# Fermento_1side.net
KiCad netlist of a schematic drawn in EAGLE
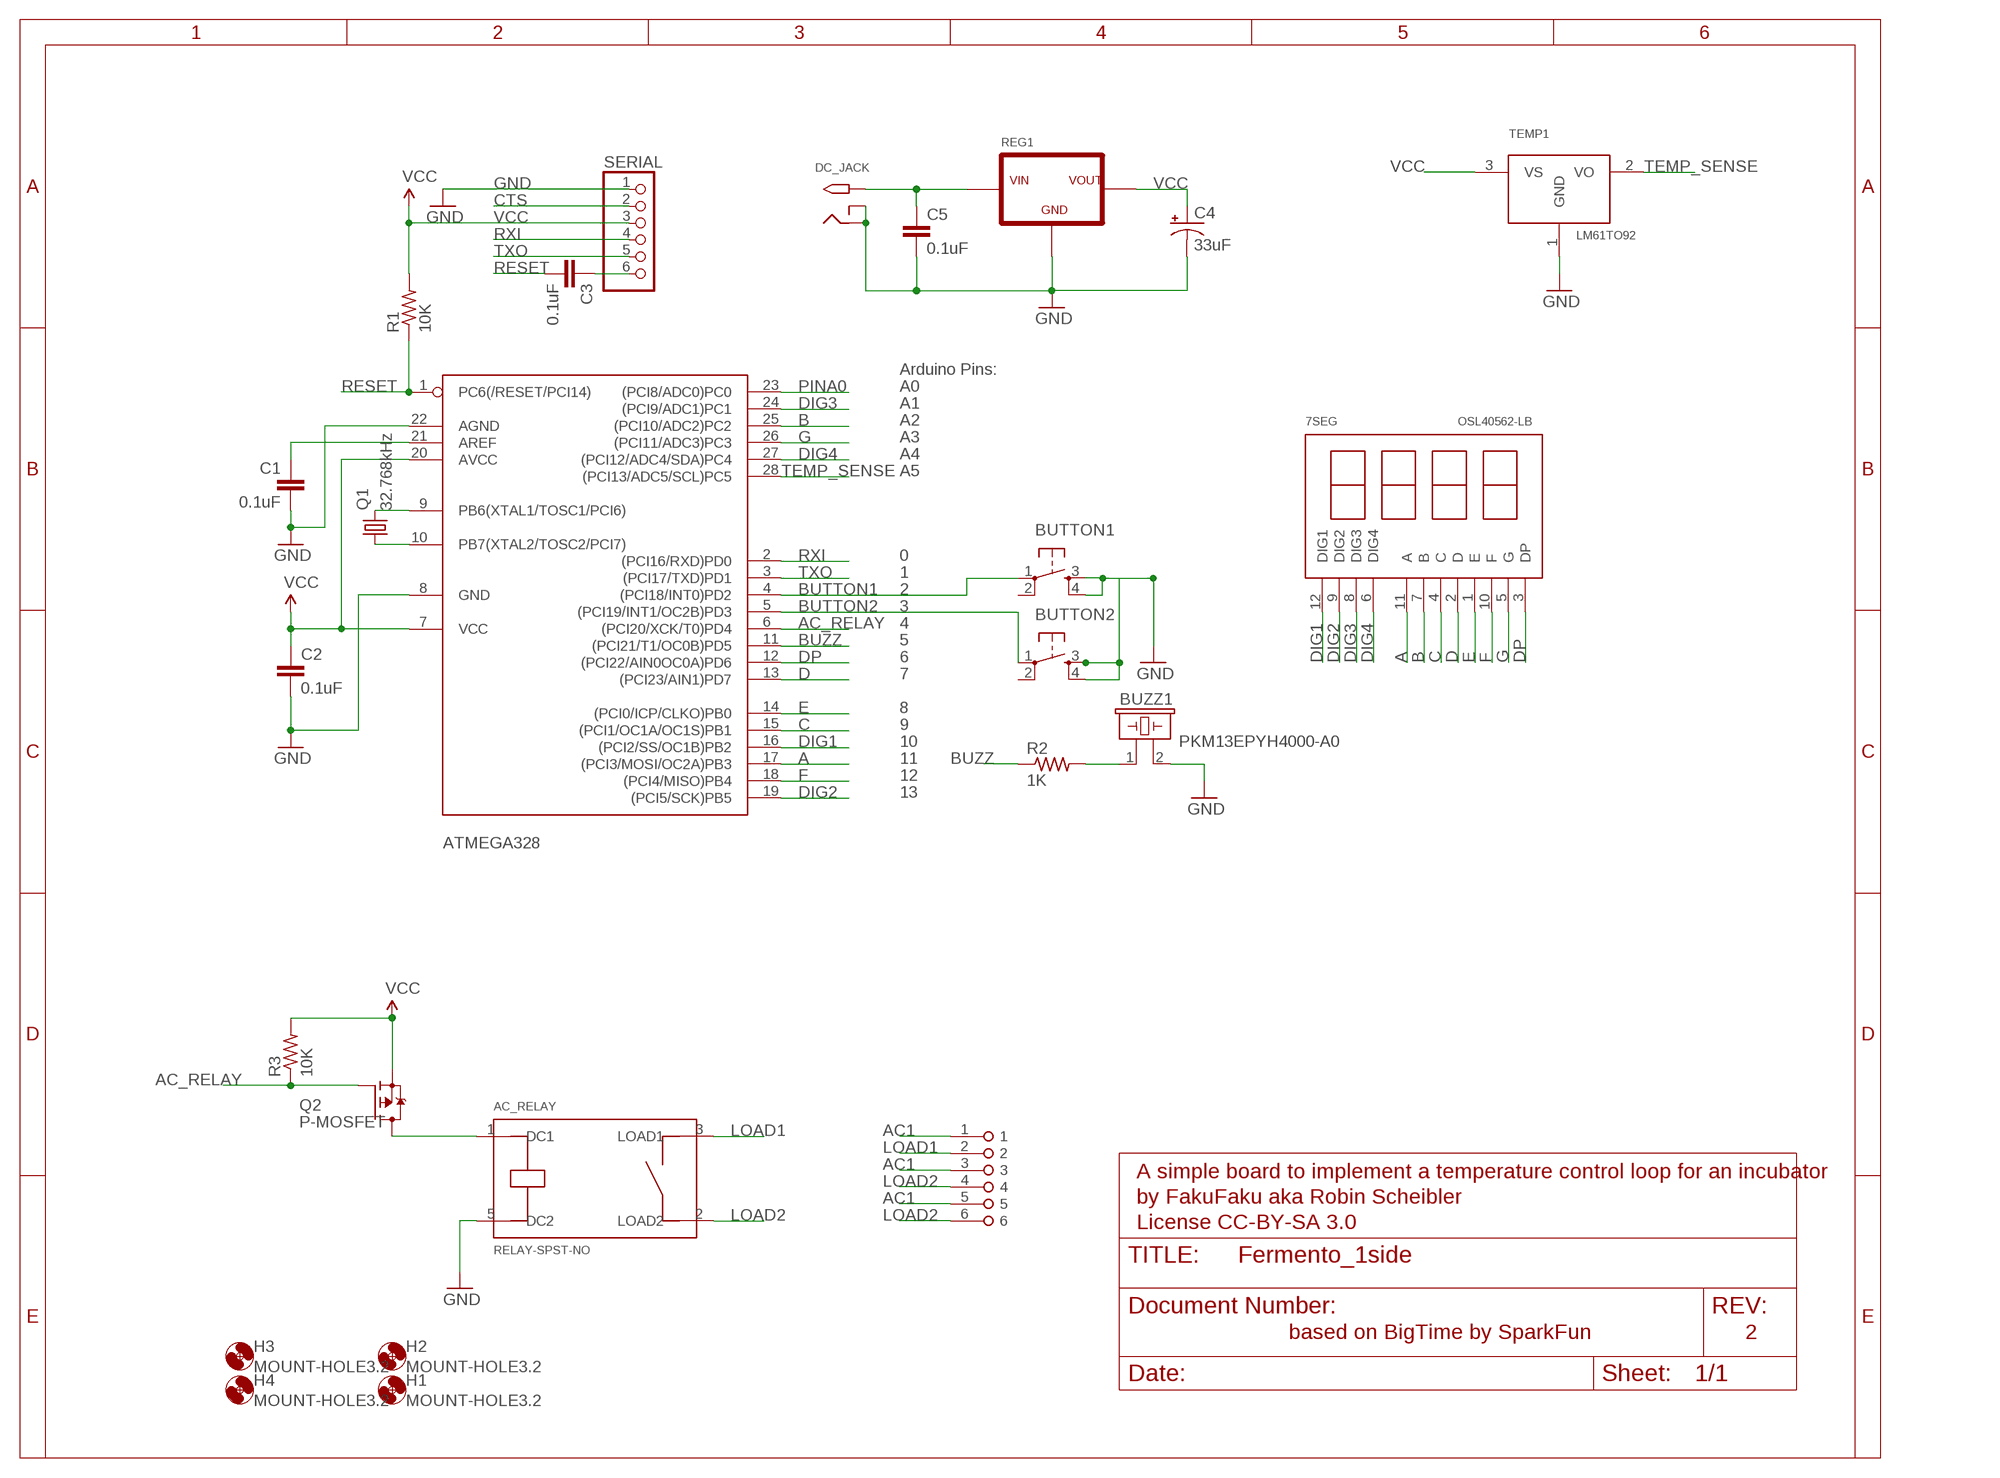
[diagram p0: schematic, sheet 1]

(export (version "E")
  (design (tool "Eeschema 10.0.6"))
  (components
    (comp (ref "7SEG")
      (value "OSL40562-LB")
      (footprint "eagle-import:OSL40562")
      (libsource (lib "eagle-import") (part "7SEG"))
    )
    (comp (ref "AC_RELAY")
      (value "RELAY-SPST-NO")
      (footprint "eagle-import:G6RL-1A-DC3")
      (libsource (lib "eagle-import") (part "RELAY-SPST-NO"))
    )
    (comp (ref "ATMEGA328")
      (value "ATMEGA168-20P")
      (footprint "eagle-import:DIL28-3")
      (libsource (lib "eagle-import") (part "ATMEGA168P-20"))
    )
    (comp (ref "BUTTON1")
      (value "TAC_SWITCHPTH")
      (footprint "eagle-import:TACTILE-PTH")
      (libsource (lib "eagle-import") (part "TAC_SWITCHPTH"))
    )
    (comp (ref "BUTTON2")
      (value "TAC_SWITCHPTH")
      (footprint "eagle-import:TACTILE-PTH")
      (libsource (lib "eagle-import") (part "TAC_SWITCHPTH"))
    )
    (comp (ref "BUZZ1")
      (value "PKM13EPYH4000-A0")
      (footprint "eagle-import:PIEZO-MURATA-13MM")
      (libsource (lib "eagle-import") (part "BUZZER13MM"))
    )
    (comp (ref "C1")
      (value "0.1uF")
      (footprint "eagle-import:CAP-PTH-SMALL")
      (libsource (lib "eagle-import") (part "CAPPTH"))
    )
    (comp (ref "C2")
      (value "0.1uF")
      (footprint "eagle-import:CAP-PTH-SMALL")
      (libsource (lib "eagle-import") (part "CAPPTH"))
    )
    (comp (ref "C3")
      (value "0.1uF")
      (footprint "eagle-import:CAP-PTH-SMALL")
      (libsource (lib "eagle-import") (part "CAPPTH"))
    )
    (comp (ref "C4")
      (value "33uF")
      (footprint "eagle-import:CPOL-RADIAL-10UF-25V")
      (libsource (lib "eagle-import") (part "CAP_POLPTH2"))
    )
    (comp (ref "C5")
      (value "0.1uF")
      (footprint "eagle-import:CAP-PTH-SMALL")
      (libsource (lib "eagle-import") (part "CAPPTH"))
    )
    (comp (ref "DC_JACK")
      (value "2.1MMJACKTHM")
      (footprint "eagle-import:PJ-102A")
      (libsource (lib "eagle-import") (part "2.1MMJACKTHM"))
    )
    (comp (ref "H1")
      (value "MOUNT-HOLE3.2")
      (footprint "eagle-import:3,2")
      (libsource (lib "eagle-import") (part "MOUNT-HOLE3.2"))
    )
    (comp (ref "H2")
      (value "MOUNT-HOLE3.2")
      (footprint "eagle-import:3,2")
      (libsource (lib "eagle-import") (part "MOUNT-HOLE3.2"))
    )
    (comp (ref "H3")
      (value "MOUNT-HOLE3.2")
      (footprint "eagle-import:3,2")
      (libsource (lib "eagle-import") (part "MOUNT-HOLE3.2"))
    )
    (comp (ref "H4")
      (value "MOUNT-HOLE3.2")
      (footprint "eagle-import:3,2")
      (libsource (lib "eagle-import") (part "MOUNT-HOLE3.2"))
    )
    (comp (ref "Q1")
      (value "32.768kHz")
      (footprint "eagle-import:CRYSTAL-8X3-TH")
      (libsource (lib "eagle-import") (part "CRYSTAL8X3"))
    )
    (comp (ref "Q2")
      (value "P-MOSFET")
      (footprint "eagle-import:TO92-")
      (libsource (lib "eagle-import") (part "P-MOSFET"))
    )
    (comp (ref "R1")
      (value "10K")
      (footprint "eagle-import:0207_10")
      (libsource (lib "eagle-import") (part "R-US_0207/10"))
    )
    (comp (ref "R2")
      (value "1K")
      (footprint "eagle-import:0207_10")
      (libsource (lib "eagle-import") (part "R-US_0207/10"))
    )
    (comp (ref "R3")
      (value "10K")
      (footprint "eagle-import:0207_10")
      (libsource (lib "eagle-import") (part "R-US_0207/10"))
    )
    (comp (ref "REG1")
      (value "REGULATOR-NOTHERMAL-TO220-STRAIGHT")
      (footprint "eagle-import:TO-220-STRAIGHT")
      (libsource (lib "eagle-import") (part "REGULATOR-NOTHERMAL-TO220-STRAIGHT"))
    )
    (comp (ref "SERIAL")
      (value "PINHD-1X6/90")
      (footprint "eagle-import:1X06_90")
      (libsource (lib "eagle-import") (part "PINHD-1X6/90"))
    )
    (comp (ref "TEMP1")
      (value "LM61TO92")
      (footprint "eagle-import:TO92-")
      (libsource (lib "eagle-import") (part "LM61TO92"))
    )
    (comp (ref "U$2")
      (value "TERMINAL-6")
      (footprint "eagle-import:MBE-156")
      (libsource (lib "eagle-import") (part "TERMINAL-6"))
    )
  )
  (nets
    (net (code "1") (name "/A") (class "Default")
      (node (ref "7SEG") (pin "11") (pinfunction "A_11") (pintype "bidirectional"))
      (node (ref "ATMEGA328") (pin "17") (pinfunction "(PCI3/MOSI/OC2A)PB3_17") (pintype "bidirectional"))
    )
    (net (code "2") (name "/AC1") (class "Default")
      (node (ref "U$2") (pin "1") (pinfunction "1_1") (pintype "bidirectional"))
      (node (ref "U$2") (pin "3") (pinfunction "3_3") (pintype "bidirectional"))
      (node (ref "U$2") (pin "5") (pinfunction "5_5") (pintype "bidirectional"))
    )
    (net (code "3") (name "/AC_RELAY") (class "Default")
      (node (ref "ATMEGA328") (pin "6") (pinfunction "(PCI20/XCK/T0)PD4_6") (pintype "bidirectional"))
      (node (ref "Q2") (pin "2") (pinfunction "G_2") (pintype "passive"))
      (node (ref "R3") (pin "1") (pinfunction "1_1") (pintype "passive"))
    )
    (net (code "4") (name "/B") (class "Default")
      (node (ref "7SEG") (pin "7") (pinfunction "B_7") (pintype "bidirectional"))
      (node (ref "ATMEGA328") (pin "25") (pinfunction "(PCI10/ADC2)PC2_25") (pintype "bidirectional"))
    )
    (net (code "5") (name "/BUTTON1") (class "Default")
      (node (ref "ATMEGA328") (pin "4") (pinfunction "(PCI18/INT0)PD2_4") (pintype "bidirectional"))
      (node (ref "BUTTON1") (pin "1") (pinfunction "1_1") (pintype "passive"))
    )
    (net (code "6") (name "/BUTTON2") (class "Default")
      (node (ref "ATMEGA328") (pin "5") (pinfunction "(PCI19/INT1/OC2B)PD3_5") (pintype "bidirectional"))
      (node (ref "BUTTON2") (pin "1") (pinfunction "1_1") (pintype "passive"))
    )
    (net (code "7") (name "/BUZZ") (class "Default")
      (node (ref "ATMEGA328") (pin "11") (pinfunction "(PCI21/T1/OC0B)PD5_11") (pintype "bidirectional"))
      (node (ref "R2") (pin "1") (pinfunction "1_1") (pintype "passive"))
    )
    (net (code "8") (name "/C") (class "Default")
      (node (ref "7SEG") (pin "4") (pinfunction "C_4") (pintype "bidirectional"))
      (node (ref "ATMEGA328") (pin "15") (pinfunction "(PCI1/OC1A/OC1S)PB1_15") (pintype "bidirectional"))
    )
    (net (code "9") (name "/CTS") (class "Default")
      (node (ref "SERIAL") (pin "2") (pinfunction "2_2") (pintype "passive"))
    )
    (net (code "10") (name "/D") (class "Default")
      (node (ref "7SEG") (pin "2") (pinfunction "D_2") (pintype "bidirectional"))
      (node (ref "ATMEGA328") (pin "13") (pinfunction "(PCI23/AIN1)PD7_13") (pintype "bidirectional"))
    )
    (net (code "11") (name "/DIG1") (class "Default")
      (node (ref "7SEG") (pin "12") (pinfunction "DIG1_12") (pintype "bidirectional"))
      (node (ref "ATMEGA328") (pin "16") (pinfunction "(PCI2/SS/OC1B)PB2_16") (pintype "bidirectional"))
    )
    (net (code "12") (name "/DIG2") (class "Default")
      (node (ref "7SEG") (pin "9") (pinfunction "DIG2_9") (pintype "bidirectional"))
      (node (ref "ATMEGA328") (pin "19") (pinfunction "(PCI5/SCK)PB5_19") (pintype "bidirectional"))
    )
    (net (code "13") (name "/DIG3") (class "Default")
      (node (ref "7SEG") (pin "8") (pinfunction "DIG3_8") (pintype "bidirectional"))
      (node (ref "ATMEGA328") (pin "24") (pinfunction "(PCI9/ADC1)PC1_24") (pintype "bidirectional"))
    )
    (net (code "14") (name "/DIG4") (class "Default")
      (node (ref "7SEG") (pin "6") (pinfunction "DIG4_6") (pintype "bidirectional"))
      (node (ref "ATMEGA328") (pin "27") (pinfunction "(PCI12/ADC4/SDA)PC4_27") (pintype "bidirectional"))
    )
    (net (code "15") (name "/DP") (class "Default")
      (node (ref "7SEG") (pin "3") (pinfunction "DP_3") (pintype "bidirectional"))
      (node (ref "ATMEGA328") (pin "12") (pinfunction "(PCI22/AIN0OC0A)PD6_12") (pintype "bidirectional"))
    )
    (net (code "16") (name "/E") (class "Default")
      (node (ref "7SEG") (pin "1") (pinfunction "E_1") (pintype "bidirectional"))
      (node (ref "ATMEGA328") (pin "14") (pinfunction "(PCI0/ICP/CLKO)PB0_14") (pintype "bidirectional"))
    )
    (net (code "17") (name "/F") (class "Default")
      (node (ref "7SEG") (pin "10") (pinfunction "F_10") (pintype "bidirectional"))
      (node (ref "ATMEGA328") (pin "18") (pinfunction "(PCI4/MISO)PB4_18") (pintype "bidirectional"))
    )
    (net (code "18") (name "/G") (class "Default")
      (node (ref "7SEG") (pin "5") (pinfunction "G_5") (pintype "bidirectional"))
      (node (ref "ATMEGA328") (pin "26") (pinfunction "(PCI11/ADC3)PC3_26") (pintype "bidirectional"))
    )
    (net (code "19") (name "/LOAD1") (class "Default")
      (node (ref "AC_RELAY") (pin "3") (pinfunction "LOAD1_3") (pintype "bidirectional"))
      (node (ref "U$2") (pin "2") (pinfunction "2_2") (pintype "bidirectional"))
    )
    (net (code "20") (name "/LOAD2") (class "Default")
      (node (ref "AC_RELAY") (pin "2") (pinfunction "LOAD2_2") (pintype "bidirectional"))
      (node (ref "U$2") (pin "4") (pinfunction "4_4") (pintype "bidirectional"))
      (node (ref "U$2") (pin "6") (pinfunction "6_6") (pintype "bidirectional"))
    )
    (net (code "21") (name "/PINA0") (class "Default")
      (node (ref "ATMEGA328") (pin "23") (pinfunction "(PCI8/ADC0)PC0_23") (pintype "bidirectional"))
    )
    (net (code "22") (name "/RESET") (class "Default")
      (node (ref "ATMEGA328") (pin "1") (pinfunction "PC6(/RESET/PCI14)_1") (pintype "bidirectional"))
      (node (ref "C3") (pin "2") (pinfunction "2_2") (pintype "passive"))
      (node (ref "R1") (pin "1") (pinfunction "1_1") (pintype "passive"))
    )
    (net (code "23") (name "/RXI") (class "Default")
      (node (ref "ATMEGA328") (pin "2") (pinfunction "(PCI16/RXD)PD0_2") (pintype "bidirectional"))
      (node (ref "SERIAL") (pin "4") (pinfunction "4_4") (pintype "passive"))
    )
    (net (code "24") (name "/TEMP_SENSE") (class "Default")
      (node (ref "ATMEGA328") (pin "28") (pinfunction "(PCI13/ADC5/SCL)PC5_28") (pintype "bidirectional"))
      (node (ref "TEMP1") (pin "2") (pinfunction "VO_2") (pintype "bidirectional"))
    )
    (net (code "25") (name "/TXO") (class "Default")
      (node (ref "ATMEGA328") (pin "3") (pinfunction "(PCI17/TXD)PD1_3") (pintype "bidirectional"))
      (node (ref "SERIAL") (pin "5") (pinfunction "5_5") (pintype "passive"))
    )
    (net (code "26") (name "GND") (class "Default")
      (node (ref "AC_RELAY") (pin "5") (pinfunction "DC2_5") (pintype "bidirectional"))
      (node (ref "ATMEGA328") (pin "22") (pinfunction "AGND_22") (pintype "bidirectional"))
      (node (ref "ATMEGA328") (pin "8") (pinfunction "GND_8") (pintype "bidirectional"))
      (node (ref "BUTTON1") (pin "3") (pinfunction "3_3") (pintype "passive"))
      (node (ref "BUTTON1") (pin "4") (pinfunction "4_4") (pintype "passive"))
      (node (ref "BUTTON2") (pin "3") (pinfunction "3_3") (pintype "passive"))
      (node (ref "BUTTON2") (pin "4") (pinfunction "4_4") (pintype "passive"))
      (node (ref "BUZZ1") (pin "2") (pinfunction "2_2") (pintype "passive"))
      (node (ref "C1") (pin "2") (pinfunction "2_2") (pintype "passive"))
      (node (ref "C2") (pin "2") (pinfunction "2_2") (pintype "passive"))
      (node (ref "C4") (pin "2") (pinfunction "-_2") (pintype "passive"))
      (node (ref "C5") (pin "2") (pinfunction "2_2") (pintype "passive"))
      (node (ref "DC_JACK") (pin "RING") (pinfunction "RING_RING") (pintype "bidirectional"))
      (node (ref "DC_JACK") (pin "RING_SW") (pinfunction "RING_SW_RING_SW") (pintype "bidirectional"))
      (node (ref "REG1") (pin "CENTER") (pinfunction "GND_CENTER") (pintype "power_in"))
      (node (ref "SERIAL") (pin "1") (pinfunction "1_1") (pintype "passive"))
      (node (ref "TEMP1") (pin "1") (pinfunction "GND_1") (pintype "bidirectional"))
    )
    (net (code "27") (name "Net-(AC_RELAY-DC1)") (class "Default")
      (node (ref "AC_RELAY") (pin "1") (pinfunction "DC1_1") (pintype "bidirectional"))
      (node (ref "Q2") (pin "1") (pinfunction "D_1") (pintype "passive"))
    )
    (net (code "28") (name "Net-(ATMEGA328-AREF)") (class "Default")
      (node (ref "ATMEGA328") (pin "21") (pinfunction "AREF_21") (pintype "bidirectional"))
      (node (ref "C1") (pin "1") (pinfunction "1_1") (pintype "passive"))
    )
    (net (code "29") (name "Net-(ATMEGA328-PB6(XTAL1{slash}TOSC1{slash}PCI6))") (class "Default")
      (node (ref "ATMEGA328") (pin "9") (pinfunction "PB6(XTAL1/TOSC1/PCI6)_9") (pintype "bidirectional"))
      (node (ref "Q1") (pin "2") (pinfunction "2_2") (pintype "passive"))
    )
    (net (code "30") (name "Net-(ATMEGA328-PB7(XTAL2{slash}TOSC2{slash}PCI7))") (class "Default")
      (node (ref "ATMEGA328") (pin "10") (pinfunction "PB7(XTAL2/TOSC2/PCI7)_10") (pintype "bidirectional"))
      (node (ref "Q1") (pin "1") (pinfunction "1_1") (pintype "passive"))
    )
    (net (code "31") (name "Net-(BUZZ1-Pad1)") (class "Default")
      (node (ref "BUZZ1") (pin "1") (pinfunction "1_1") (pintype "passive"))
      (node (ref "R2") (pin "2") (pinfunction "2_2") (pintype "passive"))
    )
    (net (code "32") (name "Net-(C3-Pad1)") (class "Default")
      (node (ref "C3") (pin "1") (pinfunction "1_1") (pintype "passive"))
      (node (ref "SERIAL") (pin "6") (pinfunction "6_6") (pintype "passive"))
    )
    (net (code "33") (name "Net-(REG1-VIN)") (class "Default")
      (node (ref "C5") (pin "1") (pinfunction "1_1") (pintype "passive"))
      (node (ref "DC_JACK") (pin "TIP") (pinfunction "TIP_TIP") (pintype "bidirectional"))
      (node (ref "REG1") (pin "LEFT") (pinfunction "VIN_LEFT") (pintype "input"))
    )
    (net (code "34") (name "VCC") (class "Default")
      (node (ref "ATMEGA328") (pin "20") (pinfunction "AVCC_20") (pintype "bidirectional"))
      (node (ref "ATMEGA328") (pin "7") (pinfunction "VCC_7") (pintype "bidirectional"))
      (node (ref "C2") (pin "1") (pinfunction "1_1") (pintype "passive"))
      (node (ref "C4") (pin "1") (pinfunction "+_1") (pintype "passive"))
      (node (ref "Q2") (pin "3") (pinfunction "S_3") (pintype "passive"))
      (node (ref "R1") (pin "2") (pinfunction "2_2") (pintype "passive"))
      (node (ref "R3") (pin "2") (pinfunction "2_2") (pintype "passive"))
      (node (ref "REG1") (pin "RIGHT") (pinfunction "VOUT_RIGHT") (pintype "power_in"))
      (node (ref "SERIAL") (pin "3") (pinfunction "3_3") (pintype "passive"))
      (node (ref "TEMP1") (pin "3") (pinfunction "VS_3") (pintype "bidirectional"))
    )
    (net (code "35") (name "unconnected-(BUTTON1-Pad2)") (class "Default")
      (node (ref "BUTTON1") (pin "2") (pinfunction "2_2") (pintype "passive"))
    )
    (net (code "36") (name "unconnected-(BUTTON2-Pad2)") (class "Default")
      (node (ref "BUTTON2") (pin "2") (pinfunction "2_2") (pintype "passive"))
    )
  )
)
